# Connectors.net
KiCad netlist of a schematic drawn in Altium Designer
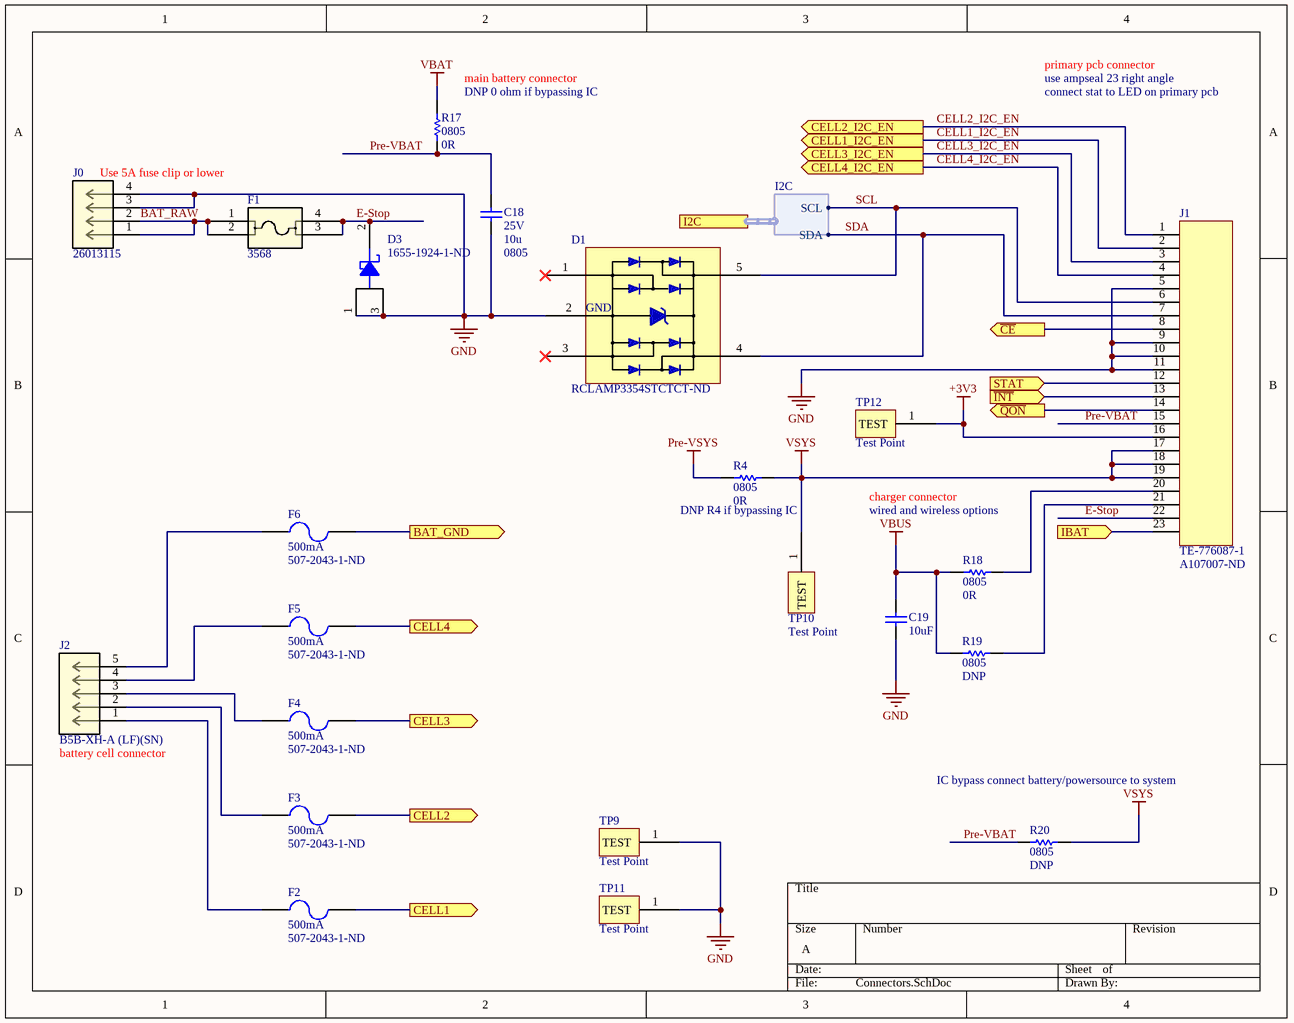
[diagram p0: Connectors.SchDoc]

(export (version "E")
  (design (tool "Eeschema 10.0.6"))
  (components
    (comp (ref "C18")
      (value "GRM21BR61E106MA73L")
      (footprint "C0805")
      (description "CAP SMD 10uF +/-20% 25V 0805")
      (fields
        (field (name "TOLERANCE") "±20%")
        (field (name "VOLTAGE - RATED") "25V")
        (field (name "CAPACITANCE") "10u")
        (field (name "PACKAGE / CASE") "0805")
      )
      (libsource (lib "Capacitors") (part "GRM21BR61E106MA73L"))
    )
    (comp (ref "C19")
      (value "Capacitor 0603")
      (footprint "C0603")
      (description "Multilayer Ceramic Capacitors (High dielectric type), 25V, 10 uF, ± 20 %, 0603, X5R, RoHS")
      (fields
        (field (name "MANUFACTURER") "Taiyo Yuden")
        (field (name "MANUFACTURER PART NUMBER") "TMK107BBJ106MA-T")
        (field (name "CAPACITANCE") "10uF")
      )
      (libsource (lib "Wally_BMS") (part "Capacitor 0603"))
    )
    (comp (ref "D1")
      (value "RCLAMP3354S.TCT")
      (footprint "SOT95P280X145-5N")
      (description "TVS DIODE 3.3VWM 16VC")
      (fields (field (name "SUPPLIER PART NUMBER 1") "RCLAMP3354STCTCT-ND"))
      (libsource (lib "Wally_BMS") (part "RCLAMP3354S.TCT"))
    )
    (comp (ref "D3")
      (value "1655-1924-1-ND")
      (footprint "50WQ06FNTR")
      (description "SCHOTTKY RECTIFIER 60V D-PAK")
      (libsource (lib "Wally_BMS") (part "50WQ06FNTR"))
    )
    (comp (ref "F1")
      (value "3568")
      (footprint "3568_KEY")
      (description "No Description Available")
      (fields (field (name "COPYRIGHT") "Copyright (C) 2022 Ultra Librarian. All rights reserved."))
      (libsource (lib "Wally_BMS") (part "3568"))
    )
    (comp (ref "F2")
      (value "Bel Fuse Inc. 0679H0500-05")
      (footprint "Bel Fuse Inc. 0679H0500-05")
      (description "FUSE BRD MNT 500MA 350VAC 72VDC")
      (fields
        (field (name "MANUFACTURER PART NUMBER") "0679H0500-05")
        (field (name "MANUFACTURER") "Bel Fuse Inc.")
        (field (name "CURRENT RATING") "500mA")
        (field (name "SUPPLIER PART NUMBER 1") "507-2043-1-ND")
      )
      (libsource (lib "Fuses") (part "Bel Fuse Inc. 0679H0500-05"))
    )
    (comp (ref "F3")
      (value "Bel Fuse Inc. 0679H0500-05")
      (footprint "Bel Fuse Inc. 0679H0500-05")
      (description "FUSE BRD MNT 500MA 350VAC 72VDC")
      (fields
        (field (name "MANUFACTURER PART NUMBER") "0679H0500-05")
        (field (name "MANUFACTURER") "Bel Fuse Inc.")
        (field (name "CURRENT RATING") "500mA")
        (field (name "SUPPLIER PART NUMBER 1") "507-2043-1-ND")
      )
      (libsource (lib "Fuses") (part "Bel Fuse Inc. 0679H0500-05"))
    )
    (comp (ref "F4")
      (value "Bel Fuse Inc. 0679H0500-05")
      (footprint "Bel Fuse Inc. 0679H0500-05")
      (description "FUSE BRD MNT 500MA 350VAC 72VDC")
      (fields
        (field (name "MANUFACTURER PART NUMBER") "0679H0500-05")
        (field (name "MANUFACTURER") "Bel Fuse Inc.")
        (field (name "CURRENT RATING") "500mA")
        (field (name "SUPPLIER PART NUMBER 1") "507-2043-1-ND")
      )
      (libsource (lib "Fuses") (part "Bel Fuse Inc. 0679H0500-05"))
    )
    (comp (ref "F5")
      (value "Bel Fuse Inc. 0679H0500-05")
      (footprint "Bel Fuse Inc. 0679H0500-05")
      (description "FUSE BRD MNT 500MA 350VAC 72VDC")
      (fields
        (field (name "MANUFACTURER PART NUMBER") "0679H0500-05")
        (field (name "MANUFACTURER") "Bel Fuse Inc.")
        (field (name "CURRENT RATING") "500mA")
        (field (name "SUPPLIER PART NUMBER 1") "507-2043-1-ND")
      )
      (libsource (lib "Fuses") (part "Bel Fuse Inc. 0679H0500-05"))
    )
    (comp (ref "F6")
      (value "Bel Fuse Inc. 0679H0500-05")
      (footprint "Bel Fuse Inc. 0679H0500-05")
      (description "FUSE BRD MNT 500MA 350VAC 72VDC")
      (fields
        (field (name "MANUFACTURER PART NUMBER") "0679H0500-05")
        (field (name "MANUFACTURER") "Bel Fuse Inc.")
        (field (name "CURRENT RATING") "500mA")
        (field (name "SUPPLIER PART NUMBER 1") "507-2043-1-ND")
      )
      (libsource (lib "Fuses") (part "Bel Fuse Inc. 0679H0500-05"))
    )
    (comp (ref "J0")
      (value "26013115")
      (footprint "CON_26013115")
      (description "Conn Power HDR 4 POS 4.2mm Solder RA Thru-Hole 4 Terminal 1 Port Bag")
      (fields
        (field (name "MANUFACTURER") "Molex")
        (field (name "MANUFACTURER PART NUMBER") "26-01-3115")
        (field (name "COPYRIGHT") "Copyright (C) 2021 Ultra Librarian. All rights reserved.")
      )
      (libsource (lib "Wally_BMS") (part "26013115"))
    )
    (comp (ref "J1")
      (value "TE-776087-1")
      (footprint "TE-776087-1")
      (description "CONN HDR RTANG 23POS W/GASKT TIN")
      (fields (field (name "SUPPLIER PART NUMBER 1") "A107007-ND"))
      (libsource (lib "Connectors and Headers") (part "TE-776087-1"))
    )
    (comp (ref "J2")
      (value "B5B-XH-A (LF)(SN)")
      (footprint "CONN_B5B-XH-A (LF)(SN)_JST")
      (description "No Description Available")
      (fields (field (name "COPYRIGHT") "Copyright (C) 2021 Ultra Librarian. All rights reserved."))
      (libsource (lib "Wally_BMS") (part "B5B-XH-A (LF)(SN)"))
    )
    (comp (ref "R4")
      (value "Resistor 0805")
      (footprint "RES0805")
      (description "Res Thick Film 0805 0 Ohm Jumper 1/8W Molded SMD Paper T/R")
      (fields
        (field (name "PACKAGE / CASE") "0805")
        (field (name "MANUFACTURER") "Stackpole Electronics")
        (field (name "MANUFACTURER PART NUMBER") "RMCF0805ZT0R00")
        (field (name "RESISTANCE") "0R")
      )
      (libsource (lib "Wally_BMS") (part "Resistor 0805"))
    )
    (comp (ref "R17")
      (value "Resistor 0805")
      (footprint "RES0805")
      (description "Res Thick Film 0805 0 Ohm Jumper 1/8W Molded SMD Paper T/R")
      (fields
        (field (name "PACKAGE / CASE") "0805")
        (field (name "MANUFACTURER") "Stackpole Electronics")
        (field (name "MANUFACTURER PART NUMBER") "RMCF0805ZT0R00")
        (field (name "RESISTANCE") "0R")
      )
      (libsource (lib "Wally_BMS") (part "Resistor 0805"))
    )
    (comp (ref "R18")
      (value "Resistor 0805")
      (footprint "RES0805")
      (description "Res Thick Film 0805 0 Ohm Jumper 1/8W Molded SMD Paper T/R")
      (fields
        (field (name "PACKAGE / CASE") "0805")
        (field (name "MANUFACTURER") "Stackpole Electronics")
        (field (name "MANUFACTURER PART NUMBER") "RMCF0805ZT0R00")
        (field (name "RESISTANCE") "0R")
      )
      (libsource (lib "Wally_BMS") (part "Resistor 0805"))
    )
    (comp (ref "R19")
      (value "Resistor 0805")
      (footprint "RES0805")
      (description "DNP")
      (fields (field (name "PACKAGE / CASE") "0805") (field (name "RESISTANCE") "DNP"))
      (libsource (lib "Wally_BMS") (part "Resistor 0805"))
    )
    (comp (ref "R20")
      (value "Resistor 0805")
      (footprint "RES0805")
      (description "DNP")
      (fields (field (name "PACKAGE / CASE") "0805") (field (name "RESISTANCE") "DNP"))
      (libsource (lib "Wally_BMS") (part "Resistor 0805"))
    )
    (comp (ref "TP9")
      (value "Test Point")
      (footprint "TEST POINT")
      (libsource (lib "Wally_BMS") (part "Test Point"))
    )
    (comp (ref "TP10")
      (value "Test Point")
      (footprint "TEST POINT")
      (libsource (lib "") (part "Test Point_1"))
    )
    (comp (ref "TP11")
      (value "Test Point")
      (footprint "TEST POINT")
      (libsource (lib "Wally_BMS") (part "Test Point"))
    )
    (comp (ref "TP12")
      (value "Test Point")
      (footprint "TEST POINT")
      (libsource (lib "Wally_BMS") (part "Test Point"))
    )
  )
  (nets
    (net (code "2") (name "+3V3") (class "Default")
      (node (ref "J1") (pin "16") (pintype "passive"))
      (node (ref "TP12") (pin "1") (pinfunction "TEST_1") (pintype "passive"))
    )
    (net (code "3") (name "/BAT_GND") (class "Default")
      (node (ref "F6") (pin "2") (pinfunction "2_2") (pintype "passive"))
    )
    (net (code "4") (name "/BAT_RAW") (class "Default")
      (node (ref "F1") (pin "1") (pinfunction "1_1") (pintype "passive"))
      (node (ref "F1") (pin "2") (pinfunction "2_2") (pintype "passive"))
      (node (ref "J0") (pin "1") (pinfunction "1_1") (pintype "passive"))
      (node (ref "J0") (pin "2") (pinfunction "2_2") (pintype "passive"))
    )
    (net (code "5") (name "/CELL1") (class "Default")
      (node (ref "F2") (pin "2") (pinfunction "2_2") (pintype "passive"))
    )
    (net (code "6") (name "/CELL1_I2C_EN") (class "Default") (node (ref "J1") (pin "2") (pintype "passive")))
    (net (code "7") (name "/CELL2") (class "Default")
      (node (ref "F3") (pin "2") (pinfunction "2_2") (pintype "passive"))
    )
    (net (code "8") (name "/CELL2_I2C_EN") (class "Default") (node (ref "J1") (pin "1") (pintype "passive")))
    (net (code "9") (name "/CELL3") (class "Default")
      (node (ref "F4") (pin "2") (pinfunction "2_2") (pintype "passive"))
    )
    (net (code "10") (name "/CELL3_I2C_EN") (class "Default") (node (ref "J1") (pin "3") (pintype "passive")))
    (net (code "11") (name "/CELL4") (class "Default")
      (node (ref "F5") (pin "2") (pinfunction "2_2") (pintype "passive"))
    )
    (net (code "12") (name "/CELL4_I2C_EN") (class "Default") (node (ref "J1") (pin "4") (pintype "passive")))
    (net (code "13") (name "/E-Stop") (class "Default")
      (node (ref "D3") (pin "2") (pinfunction "CATHODE_2") (pintype "passive"))
      (node (ref "F1") (pin "3") (pinfunction "3_3") (pintype "passive"))
      (node (ref "F1") (pin "4") (pinfunction "4_4") (pintype "passive"))
      (node (ref "J1") (pin "22") (pintype "passive"))
    )
    (net (code "14") (name "/IBAT") (class "Default") (node (ref "J1") (pin "23") (pintype "passive")))
    (net (code "15") (name "/Pre-VBAT") (class "Default")
      (node (ref "C18") (pin "2") (pinfunction "2_2") (pintype "passive"))
      (node (ref "J1") (pin "15") (pintype "passive"))
      (node (ref "R17") (pin "1") (pinfunction "1_1") (pintype "passive"))
      (node (ref "R20") (pin "1") (pinfunction "1_1") (pintype "passive"))
    )
    (net (code "16") (name "/SCL") (class "Default")
      (node (ref "D1") (pin "5") (pinfunction "5_5") (pintype "passive"))
      (node (ref "J1") (pin "6") (pintype "passive"))
    )
    (net (code "17") (name "/SDA") (class "Default")
      (node (ref "D1") (pin "4") (pinfunction "4_4") (pintype "passive"))
      (node (ref "J1") (pin "7") (pintype "passive"))
    )
    (net (code "18") (name "/STAT") (class "Default") (node (ref "J1") (pin "12") (pintype "passive")))
    (net (code "20") (name "/~{CE}") (class "Default") (node (ref "J1") (pin "8") (pintype "passive")))
    (net (code "21") (name "/~{INT}") (class "Default") (node (ref "J1") (pin "13") (pintype "passive")))
    (net (code "22") (name "/~{QON}") (class "Default") (node (ref "J1") (pin "14") (pintype "passive")))
    (net (code "23") (name "GND") (class "Default")
      (node (ref "C18") (pin "1") (pinfunction "1_1") (pintype "passive"))
      (node (ref "C19") (pin "1") (pinfunction "1_1") (pintype "passive"))
      (node (ref "D1") (pin "2") (pinfunction "GND_2") (pintype "power_in"))
      (node (ref "D3") (pin "1") (pinfunction "ANODE_1") (pintype "passive"))
      (node (ref "D3") (pin "3") (pinfunction "ANODE_3") (pintype "passive"))
      (node (ref "J0") (pin "3") (pinfunction "3_3") (pintype "passive"))
      (node (ref "J0") (pin "4") (pinfunction "4_4") (pintype "passive"))
      (node (ref "J1") (pin "10") (pintype "passive"))
      (node (ref "J1") (pin "11") (pintype "passive"))
      (node (ref "J1") (pin "5") (pintype "passive"))
      (node (ref "J1") (pin "9") (pintype "passive"))
      (node (ref "TP11") (pin "1") (pinfunction "TEST_1") (pintype "passive"))
      (node (ref "TP9") (pin "1") (pinfunction "TEST_1") (pintype "passive"))
    )
    (net (code "24") (name "Net-(F2-Pad1)") (class "Default")
      (node (ref "F2") (pin "1") (pinfunction "1_1") (pintype "passive"))
      (node (ref "J2") (pin "1") (pinfunction "1_1") (pintype "passive"))
    )
    (net (code "25") (name "Net-(F3-Pad1)") (class "Default")
      (node (ref "F3") (pin "1") (pinfunction "1_1") (pintype "passive"))
      (node (ref "J2") (pin "2") (pinfunction "2_2") (pintype "passive"))
    )
    (net (code "26") (name "Net-(F4-Pad1)") (class "Default")
      (node (ref "F4") (pin "1") (pinfunction "1_1") (pintype "passive"))
      (node (ref "J2") (pin "3") (pinfunction "3_3") (pintype "passive"))
    )
    (net (code "27") (name "Net-(F5-Pad1)") (class "Default")
      (node (ref "F5") (pin "1") (pinfunction "1_1") (pintype "passive"))
      (node (ref "J2") (pin "4") (pinfunction "4_4") (pintype "passive"))
    )
    (net (code "28") (name "Net-(F6-Pad1)") (class "Default")
      (node (ref "F6") (pin "1") (pinfunction "1_1") (pintype "passive"))
      (node (ref "J2") (pin "5") (pinfunction "5_5") (pintype "passive"))
    )
    (net (code "29") (name "Net-(J1-Pad20)") (class "Default")
      (node (ref "J1") (pin "20") (pintype "passive"))
      (node (ref "R18") (pin "1") (pinfunction "1_1") (pintype "passive"))
    )
    (net (code "30") (name "Net-(J1-Pad21)") (class "Default")
      (node (ref "J1") (pin "21") (pintype "passive"))
      (node (ref "R19") (pin "2") (pinfunction "2_2") (pintype "passive"))
    )
    (net (code "31") (name "Pre-VSYS") (class "Default")
      (node (ref "R4") (pin "2") (pinfunction "2_2") (pintype "passive"))
    )
    (net (code "32") (name "VBAT") (class "Default")
      (node (ref "R17") (pin "2") (pinfunction "2_2") (pintype "passive"))
    )
    (net (code "33") (name "VBUS") (class "Default")
      (node (ref "C19") (pin "2") (pinfunction "2_2") (pintype "passive"))
      (node (ref "R18") (pin "2") (pinfunction "2_2") (pintype "passive"))
      (node (ref "R19") (pin "1") (pinfunction "1_1") (pintype "passive"))
    )
    (net (code "34") (name "VSYS") (class "Default")
      (node (ref "J1") (pin "17") (pintype "passive"))
      (node (ref "J1") (pin "18") (pintype "passive"))
      (node (ref "J1") (pin "19") (pintype "passive"))
      (node (ref "R20") (pin "2") (pinfunction "2_2") (pintype "passive"))
      (node (ref "R4") (pin "1") (pinfunction "1_1") (pintype "passive"))
      (node (ref "TP10") (pin "1") (pinfunction "TEST_1") (pintype "passive"))
    )
    (net (code "35") (name "unconnected-(D1-Pad1)") (class "Default")
      (node (ref "D1") (pin "1") (pinfunction "1_1") (pintype "passive+no_connect"))
    )
    (net (code "36") (name "unconnected-(D1-Pad3)") (class "Default")
      (node (ref "D1") (pin "3") (pinfunction "3_3") (pintype "passive+no_connect"))
    )
  )
)
